# 8LedBoard.net
KiCad netlist of a schematic drawn in EAGLE
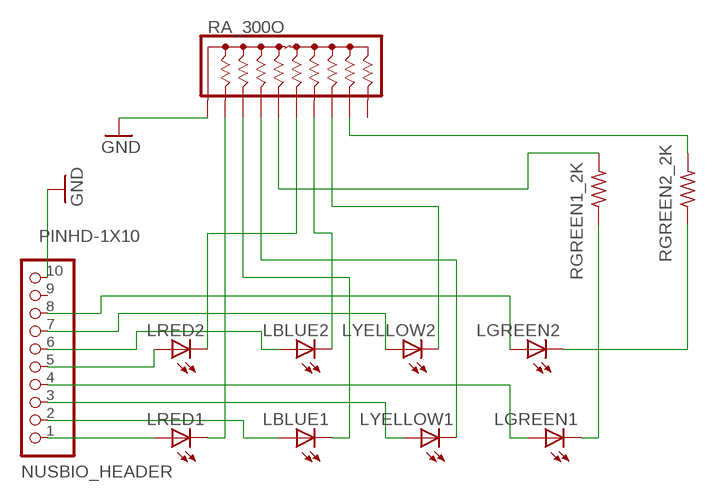
[diagram p0: schematic, sheet 1]

(export (version "E")
  (design (tool "Eeschema 10.0.6"))
  (components
    (comp (ref "LBLUE1")
      (value "LED5MM")
      (footprint "eagle-import:LED5MM")
      (libsource (lib "eagle-import") (part "LED5MM"))
    )
    (comp (ref "LBLUE2")
      (value "LED5MM")
      (footprint "eagle-import:LED5MM")
      (libsource (lib "eagle-import") (part "LED5MM"))
    )
    (comp (ref "LGREEN1")
      (value "LED5MM")
      (footprint "eagle-import:LED5MM")
      (libsource (lib "eagle-import") (part "LED5MM"))
    )
    (comp (ref "LGREEN2")
      (value "LED5MM")
      (footprint "eagle-import:LED5MM")
      (libsource (lib "eagle-import") (part "LED5MM"))
    )
    (comp (ref "LRED1")
      (value "LED5MM")
      (footprint "eagle-import:LED5MM")
      (libsource (lib "eagle-import") (part "LED5MM"))
    )
    (comp (ref "LRED2")
      (value "LED5MM")
      (footprint "eagle-import:LED5MM")
      (libsource (lib "eagle-import") (part "LED5MM"))
    )
    (comp (ref "LYELLOW1")
      (value "LED5MM")
      (footprint "eagle-import:LED5MM")
      (libsource (lib "eagle-import") (part "LED5MM"))
    )
    (comp (ref "LYELLOW2")
      (value "LED5MM")
      (footprint "eagle-import:LED5MM")
      (libsource (lib "eagle-import") (part "LED5MM"))
    )
    (comp (ref "NUSBIO_HEADER")
      (value "PINHD-1X10")
      (footprint "eagle-import:1X10-BIG")
      (libsource (lib "eagle-import") (part "PINHD-1X10"))
    )
    (comp (ref "RA_300O")
      (value "4610X")
      (footprint "eagle-import:SIP10")
      (libsource (lib "eagle-import") (part "4610X"))
    )
    (comp (ref "RGREEN1_2K")
      (value "R-US_0207/10")
      (footprint "eagle-import:0207_10")
      (libsource (lib "eagle-import") (part "R-US_0207/10"))
    )
    (comp (ref "RGREEN2_2K")
      (value "R-US_0207/10")
      (footprint "eagle-import:0207_10")
      (libsource (lib "eagle-import") (part "R-US_0207/10"))
    )
  )
  (nets
    (net (code "1") (name "GND") (class "Default")
      (node (ref "NUSBIO_HEADER") (pin "10") (pinfunction "10_10") (pintype "passive"))
      (node (ref "RA_300O") (pin "1") (pinfunction "1_1") (pintype "passive"))
    )
    (net (code "2") (name "Net-(LBLUE1-C)") (class "Default")
      (node (ref "LBLUE1") (pin "K") (pinfunction "C_K") (pintype "passive"))
      (node (ref "RA_300O") (pin "3") (pinfunction "3_3") (pintype "passive"))
    )
    (net (code "3") (name "Net-(LBLUE1-PadA)") (class "Default")
      (node (ref "LBLUE1") (pin "A") (pinfunction "A_A") (pintype "passive"))
      (node (ref "NUSBIO_HEADER") (pin "2") (pinfunction "2_2") (pintype "passive"))
    )
    (net (code "4") (name "Net-(LBLUE2-C)") (class "Default")
      (node (ref "LBLUE2") (pin "K") (pinfunction "C_K") (pintype "passive"))
      (node (ref "RA_300O") (pin "7") (pinfunction "7_7") (pintype "passive"))
    )
    (net (code "5") (name "Net-(LBLUE2-PadA)") (class "Default")
      (node (ref "LBLUE2") (pin "A") (pinfunction "A_A") (pintype "passive"))
      (node (ref "NUSBIO_HEADER") (pin "6") (pinfunction "6_6") (pintype "passive"))
    )
    (net (code "6") (name "Net-(LGREEN1-C)") (class "Default")
      (node (ref "LGREEN1") (pin "K") (pinfunction "C_K") (pintype "passive"))
      (node (ref "RGREEN1_2K") (pin "1") (pinfunction "1_1") (pintype "passive"))
    )
    (net (code "7") (name "Net-(LGREEN1-PadA)") (class "Default")
      (node (ref "LGREEN1") (pin "A") (pinfunction "A_A") (pintype "passive"))
      (node (ref "NUSBIO_HEADER") (pin "4") (pinfunction "4_4") (pintype "passive"))
    )
    (net (code "8") (name "Net-(LGREEN2-C)") (class "Default")
      (node (ref "LGREEN2") (pin "K") (pinfunction "C_K") (pintype "passive"))
      (node (ref "RGREEN2_2K") (pin "1") (pinfunction "1_1") (pintype "passive"))
    )
    (net (code "9") (name "Net-(LGREEN2-PadA)") (class "Default")
      (node (ref "LGREEN2") (pin "A") (pinfunction "A_A") (pintype "passive"))
      (node (ref "NUSBIO_HEADER") (pin "8") (pinfunction "8_8") (pintype "passive"))
    )
    (net (code "10") (name "Net-(LRED1-C)") (class "Default")
      (node (ref "LRED1") (pin "K") (pinfunction "C_K") (pintype "passive"))
      (node (ref "RA_300O") (pin "2") (pinfunction "2_2") (pintype "passive"))
    )
    (net (code "11") (name "Net-(LRED1-PadA)") (class "Default")
      (node (ref "LRED1") (pin "A") (pinfunction "A_A") (pintype "passive"))
      (node (ref "NUSBIO_HEADER") (pin "1") (pinfunction "1_1") (pintype "passive"))
    )
    (net (code "12") (name "Net-(LRED2-C)") (class "Default")
      (node (ref "LRED2") (pin "K") (pinfunction "C_K") (pintype "passive"))
      (node (ref "RA_300O") (pin "6") (pinfunction "6_6") (pintype "passive"))
    )
    (net (code "13") (name "Net-(LRED2-PadA)") (class "Default")
      (node (ref "LRED2") (pin "A") (pinfunction "A_A") (pintype "passive"))
      (node (ref "NUSBIO_HEADER") (pin "5") (pinfunction "5_5") (pintype "passive"))
    )
    (net (code "14") (name "Net-(LYELLOW1-C)") (class "Default")
      (node (ref "LYELLOW1") (pin "K") (pinfunction "C_K") (pintype "passive"))
      (node (ref "RA_300O") (pin "4") (pinfunction "4_4") (pintype "passive"))
    )
    (net (code "15") (name "Net-(LYELLOW1-PadA)") (class "Default")
      (node (ref "LYELLOW1") (pin "A") (pinfunction "A_A") (pintype "passive"))
      (node (ref "NUSBIO_HEADER") (pin "3") (pinfunction "3_3") (pintype "passive"))
    )
    (net (code "16") (name "Net-(LYELLOW2-C)") (class "Default")
      (node (ref "LYELLOW2") (pin "K") (pinfunction "C_K") (pintype "passive"))
      (node (ref "RA_300O") (pin "8") (pinfunction "8_8") (pintype "passive"))
    )
    (net (code "17") (name "Net-(LYELLOW2-PadA)") (class "Default")
      (node (ref "LYELLOW2") (pin "A") (pinfunction "A_A") (pintype "passive"))
      (node (ref "NUSBIO_HEADER") (pin "7") (pinfunction "7_7") (pintype "passive"))
    )
    (net (code "18") (name "Net-(RA_300O-Pad5)") (class "Default")
      (node (ref "RA_300O") (pin "5") (pinfunction "5_5") (pintype "passive"))
      (node (ref "RGREEN1_2K") (pin "2") (pinfunction "2_2") (pintype "passive"))
    )
    (net (code "19") (name "Net-(RA_300O-Pad9)") (class "Default")
      (node (ref "RA_300O") (pin "9") (pinfunction "9_9") (pintype "passive"))
      (node (ref "RGREEN2_2K") (pin "2") (pinfunction "2_2") (pintype "passive"))
    )
    (net (code "20") (name "unconnected-(NUSBIO_HEADER-Pad9)") (class "Default")
      (node (ref "NUSBIO_HEADER") (pin "9") (pinfunction "9_9") (pintype "passive"))
    )
    (net (code "21") (name "unconnected-(RA_300O-Pad10)") (class "Default")
      (node (ref "RA_300O") (pin "10") (pinfunction "10_10") (pintype "passive"))
    )
  )
)
